# New_Wind_Vane.net
KiCad netlist of a schematic drawn in EAGLE
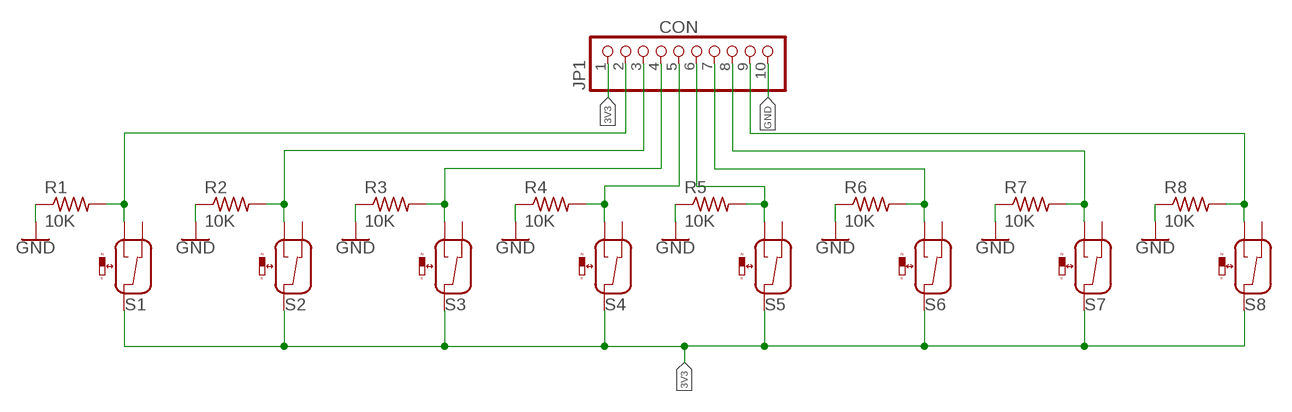
[diagram p0: schematic, sheet 1]

(export (version "E")
  (design (tool "Eeschema 10.0.6"))
  (components
    (comp (ref "JP1")
      (value "CON")
      (footprint "eagle-import:1X10_90")
      (libsource (lib "eagle-import") (part "PINHD-1X10/90"))
    )
    (comp (ref "R1")
      (value "10K")
      (footprint "eagle-import:R1206")
      (libsource (lib "eagle-import") (part "R-US_R1206"))
    )
    (comp (ref "R2")
      (value "10K")
      (footprint "eagle-import:R1206")
      (libsource (lib "eagle-import") (part "R-US_R1206"))
    )
    (comp (ref "R3")
      (value "10K")
      (footprint "eagle-import:R1206")
      (libsource (lib "eagle-import") (part "R-US_R1206"))
    )
    (comp (ref "R4")
      (value "10K")
      (footprint "eagle-import:R1206")
      (libsource (lib "eagle-import") (part "R-US_R1206"))
    )
    (comp (ref "R5")
      (value "10K")
      (footprint "eagle-import:R1206")
      (libsource (lib "eagle-import") (part "R-US_R1206"))
    )
    (comp (ref "R6")
      (value "10K")
      (footprint "eagle-import:R1206")
      (libsource (lib "eagle-import") (part "R-US_R1206"))
    )
    (comp (ref "R7")
      (value "10K")
      (footprint "eagle-import:R1206")
      (libsource (lib "eagle-import") (part "R-US_R1206"))
    )
    (comp (ref "R8")
      (value "10K")
      (footprint "eagle-import:R1206")
      (libsource (lib "eagle-import") (part "R-US_R1206"))
    )
    (comp (ref "S1")
      (value "REED-SWITCH-NO-NC")
      (footprint "eagle-import:MK6-8-C")
      (libsource (lib "eagle-import") (part "REED-SWITCH-NO-NC"))
    )
    (comp (ref "S2")
      (value "REED-SWITCH-NO-NC")
      (footprint "eagle-import:MK6-8-C")
      (libsource (lib "eagle-import") (part "REED-SWITCH-NO-NC"))
    )
    (comp (ref "S3")
      (value "REED-SWITCH-NO-NC")
      (footprint "eagle-import:MK6-8-C")
      (libsource (lib "eagle-import") (part "REED-SWITCH-NO-NC"))
    )
    (comp (ref "S4")
      (value "REED-SWITCH-NO-NC")
      (footprint "eagle-import:MK6-8-C")
      (libsource (lib "eagle-import") (part "REED-SWITCH-NO-NC"))
    )
    (comp (ref "S5")
      (value "REED-SWITCH-NO-NC")
      (footprint "eagle-import:MK6-8-C")
      (libsource (lib "eagle-import") (part "REED-SWITCH-NO-NC"))
    )
    (comp (ref "S6")
      (value "REED-SWITCH-NO-NC")
      (footprint "eagle-import:MK6-8-C")
      (libsource (lib "eagle-import") (part "REED-SWITCH-NO-NC"))
    )
    (comp (ref "S7")
      (value "REED-SWITCH-NO-NC")
      (footprint "eagle-import:MK6-8-C")
      (libsource (lib "eagle-import") (part "REED-SWITCH-NO-NC"))
    )
    (comp (ref "S8")
      (value "REED-SWITCH-NO-NC")
      (footprint "eagle-import:MK6-8-C")
      (libsource (lib "eagle-import") (part "REED-SWITCH-NO-NC"))
    )
  )
  (nets
    (net (code "1") (name "3V3") (class "Default")
      (node (ref "JP1") (pin "1") (pinfunction "1_1") (pintype "passive"))
      (node (ref "S1") (pin "COM") (pinfunction "COM_COM") (pintype "passive"))
      (node (ref "S2") (pin "COM") (pinfunction "COM_COM") (pintype "passive"))
      (node (ref "S3") (pin "COM") (pinfunction "COM_COM") (pintype "passive"))
      (node (ref "S4") (pin "COM") (pinfunction "COM_COM") (pintype "passive"))
      (node (ref "S5") (pin "COM") (pinfunction "COM_COM") (pintype "passive"))
      (node (ref "S6") (pin "COM") (pinfunction "COM_COM") (pintype "passive"))
      (node (ref "S7") (pin "COM") (pinfunction "COM_COM") (pintype "passive"))
      (node (ref "S8") (pin "COM") (pinfunction "COM_COM") (pintype "passive"))
    )
    (net (code "2") (name "GND") (class "Default")
      (node (ref "JP1") (pin "10") (pinfunction "10_10") (pintype "passive"))
      (node (ref "R1") (pin "1") (pinfunction "1_1") (pintype "passive"))
      (node (ref "R2") (pin "1") (pinfunction "1_1") (pintype "passive"))
      (node (ref "R3") (pin "1") (pinfunction "1_1") (pintype "passive"))
      (node (ref "R4") (pin "1") (pinfunction "1_1") (pintype "passive"))
      (node (ref "R5") (pin "1") (pinfunction "1_1") (pintype "passive"))
      (node (ref "R6") (pin "1") (pinfunction "1_1") (pintype "passive"))
      (node (ref "R7") (pin "1") (pinfunction "1_1") (pintype "passive"))
      (node (ref "R8") (pin "1") (pinfunction "1_1") (pintype "passive"))
    )
    (net (code "3") (name "Net-(JP1-Pad2)") (class "Default")
      (node (ref "JP1") (pin "2") (pinfunction "2_2") (pintype "passive"))
      (node (ref "R1") (pin "2") (pinfunction "2_2") (pintype "passive"))
      (node (ref "S1") (pin "NO") (pinfunction "NO_NO") (pintype "passive"))
    )
    (net (code "4") (name "Net-(JP1-Pad3)") (class "Default")
      (node (ref "JP1") (pin "3") (pinfunction "3_3") (pintype "passive"))
      (node (ref "R2") (pin "2") (pinfunction "2_2") (pintype "passive"))
      (node (ref "S2") (pin "NO") (pinfunction "NO_NO") (pintype "passive"))
    )
    (net (code "5") (name "Net-(JP1-Pad4)") (class "Default")
      (node (ref "JP1") (pin "4") (pinfunction "4_4") (pintype "passive"))
      (node (ref "R3") (pin "2") (pinfunction "2_2") (pintype "passive"))
      (node (ref "S3") (pin "NO") (pinfunction "NO_NO") (pintype "passive"))
    )
    (net (code "6") (name "Net-(JP1-Pad5)") (class "Default")
      (node (ref "JP1") (pin "5") (pinfunction "5_5") (pintype "passive"))
      (node (ref "R4") (pin "2") (pinfunction "2_2") (pintype "passive"))
      (node (ref "S4") (pin "NO") (pinfunction "NO_NO") (pintype "passive"))
    )
    (net (code "7") (name "Net-(JP1-Pad6)") (class "Default")
      (node (ref "JP1") (pin "6") (pinfunction "6_6") (pintype "passive"))
      (node (ref "R5") (pin "2") (pinfunction "2_2") (pintype "passive"))
      (node (ref "S5") (pin "NO") (pinfunction "NO_NO") (pintype "passive"))
    )
    (net (code "8") (name "Net-(JP1-Pad7)") (class "Default")
      (node (ref "JP1") (pin "7") (pinfunction "7_7") (pintype "passive"))
      (node (ref "R6") (pin "2") (pinfunction "2_2") (pintype "passive"))
      (node (ref "S6") (pin "NO") (pinfunction "NO_NO") (pintype "passive"))
    )
    (net (code "9") (name "Net-(JP1-Pad8)") (class "Default")
      (node (ref "JP1") (pin "8") (pinfunction "8_8") (pintype "passive"))
      (node (ref "R7") (pin "2") (pinfunction "2_2") (pintype "passive"))
      (node (ref "S7") (pin "NO") (pinfunction "NO_NO") (pintype "passive"))
    )
    (net (code "10") (name "Net-(JP1-Pad9)") (class "Default")
      (node (ref "JP1") (pin "9") (pinfunction "9_9") (pintype "passive"))
      (node (ref "R8") (pin "2") (pinfunction "2_2") (pintype "passive"))
      (node (ref "S8") (pin "NO") (pinfunction "NO_NO") (pintype "passive"))
    )
    (net (code "11") (name "unconnected-(S1-PadNC)") (class "Default")
      (node (ref "S1") (pin "NC") (pinfunction "NC_NC") (pintype "passive"))
    )
    (net (code "12") (name "unconnected-(S2-PadNC)") (class "Default")
      (node (ref "S2") (pin "NC") (pinfunction "NC_NC") (pintype "passive"))
    )
    (net (code "13") (name "unconnected-(S3-PadNC)") (class "Default")
      (node (ref "S3") (pin "NC") (pinfunction "NC_NC") (pintype "passive"))
    )
    (net (code "14") (name "unconnected-(S4-PadNC)") (class "Default")
      (node (ref "S4") (pin "NC") (pinfunction "NC_NC") (pintype "passive"))
    )
    (net (code "15") (name "unconnected-(S5-PadNC)") (class "Default")
      (node (ref "S5") (pin "NC") (pinfunction "NC_NC") (pintype "passive"))
    )
    (net (code "16") (name "unconnected-(S6-PadNC)") (class "Default")
      (node (ref "S6") (pin "NC") (pinfunction "NC_NC") (pintype "passive"))
    )
    (net (code "17") (name "unconnected-(S7-PadNC)") (class "Default")
      (node (ref "S7") (pin "NC") (pinfunction "NC_NC") (pintype "passive"))
    )
    (net (code "18") (name "unconnected-(S8-PadNC)") (class "Default")
      (node (ref "S8") (pin "NC") (pinfunction "NC_NC") (pintype "passive"))
    )
  )
)
